# X4.net
KiCad netlist of a schematic drawn in Altium Designer
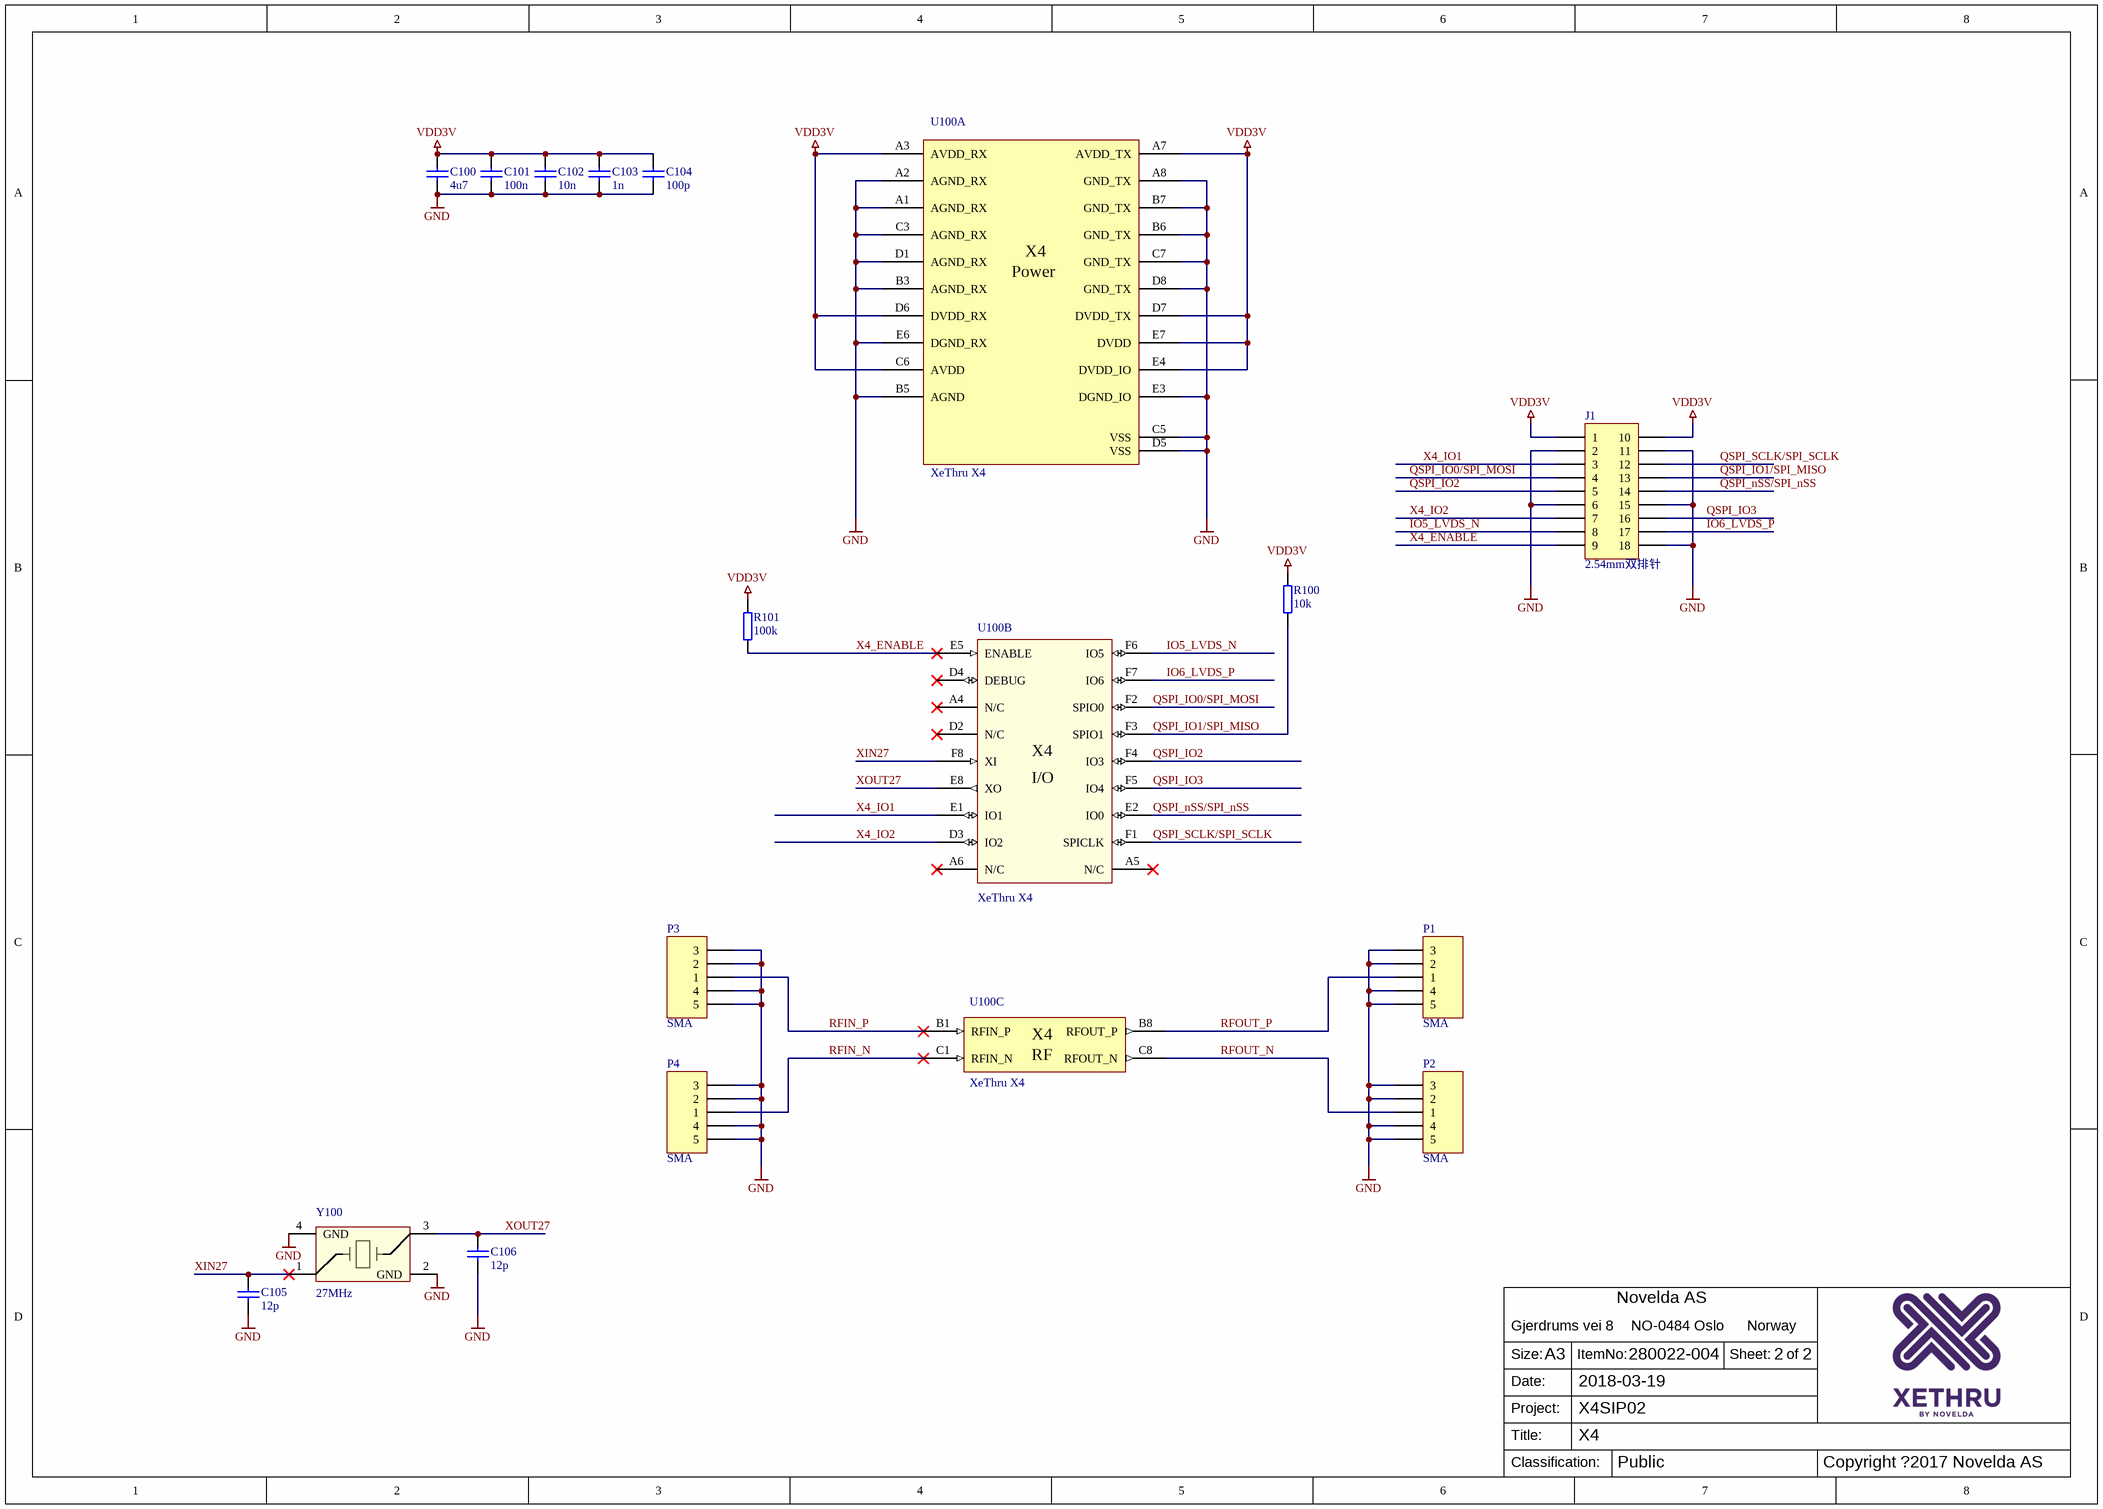
[diagram p0: X4.SchDoc]

(export (version "E")
  (design (tool "Eeschema 10.0.6"))
  (components
    (comp (ref "C100")
      (value "4u7")
      (footprint "0603-CAPACITOR-NONPOL")
      (description "CAPACITOR, 4u7, 0603, 10%, 10V, X5R")
      (fields (field (name "MANUFACTURER") "--"))
      (libsource (lib "novelda_altiumlib") (part "CAPACITOR-NONPOL"))
    )
    (comp (ref "C101")
      (value "100n")
      (footprint "0402-CAPACITOR-NONPOL")
      (description "CAPACITOR, 100n, 0402, 10%, 10V, X5R")
      (fields (field (name "MANUFACTURER") "--"))
      (libsource (lib "novelda_altiumlib") (part "CAPACITOR-NONPOL"))
    )
    (comp (ref "C102")
      (value "10n")
      (footprint "0402-CAPACITOR-NONPOL")
      (description "CAPACITOR, 10n, 0402, 10%, 25V, X7R")
      (fields (field (name "MANUFACTURER") "--"))
      (libsource (lib "novelda_altiumlib") (part "CAPACITOR-NONPOL"))
    )
    (comp (ref "C103")
      (value "1n")
      (footprint "0402-CAPACITOR-NONPOL")
      (description "CAPACITOR, 1n, 0402, 10%, 25V, X7R")
      (fields (field (name "MANUFACTURER") "--"))
      (libsource (lib "novelda_altiumlib") (part "CAPACITOR-NONPOL"))
    )
    (comp (ref "C104")
      (value "100p")
      (footprint "0402-CAPACITOR-NONPOL")
      (description "CAPACITOR, 100p, 0402, 20%, 50V, X7R")
      (fields (field (name "MANUFACTURER") "--"))
      (libsource (lib "novelda_altiumlib") (part "CAPACITOR-NONPOL"))
    )
    (comp (ref "C105")
      (value "12p")
      (footprint "0402-CAPACITOR-NONPOL")
      (description "CAPACITOR, 12p, 0402, 5%, 50V, NP0")
      (fields (field (name "MANUFACTURER") "--"))
      (libsource (lib "novelda_altiumlib") (part "CAPACITOR-NONPOL"))
    )
    (comp (ref "C106")
      (value "12p")
      (footprint "0402-CAPACITOR-NONPOL")
      (description "CAPACITOR, 12p, 0402, 5%, 50V, NP0")
      (fields (field (name "MANUFACTURER") "--"))
      (libsource (lib "novelda_altiumlib") (part "CAPACITOR-NONPOL"))
    )
    (comp (ref "J1")
      (value "2.54mm双排针")
      (footprint "HDR2X9_CEN")
      (description "Header, 9-Pin, Dual row")
      (fields (field (name "PUBLISHER") "Altium Limited"))
      (libsource (lib "Miscellaneous Connectors") (part "Header 9X2A"))
    )
    (comp (ref "P1")
      (value "SMA")
      (footprint "SMD3")
      (description "Header, 5-Pin")
      (fields (field (name "PUBLISHER") "Altium Limited"))
      (libsource (lib "Miscellaneous Connectors") (part "Header 5"))
    )
    (comp (ref "P2")
      (value "SMA")
      (footprint "SMD3")
      (description "Header, 5-Pin")
      (fields (field (name "PUBLISHER") "Altium Limited"))
      (libsource (lib "Miscellaneous Connectors") (part "Header 5"))
    )
    (comp (ref "P3")
      (value "SMA")
      (footprint "SMD3")
      (description "Header, 5-Pin")
      (fields (field (name "PUBLISHER") "Altium Limited"))
      (libsource (lib "") (part "Header 5_1"))
    )
    (comp (ref "P4")
      (value "SMA")
      (footprint "SMD3")
      (description "Header, 5-Pin")
      (fields (field (name "PUBLISHER") "Altium Limited"))
      (libsource (lib "") (part "Header 5_1"))
    )
    (comp (ref "R100")
      (value "10k")
      (footprint "0402-RESISTOR")
      (description "RESISTOR, 10k, 0402, 1%, 63mW")
      (fields (field (name "MANUFACTURER") "--"))
      (libsource (lib "novelda_altiumlib") (part "RESISTOR"))
    )
    (comp (ref "R101")
      (value "100k")
      (footprint "0402-RESISTOR")
      (description "RESISTOR, 100k, 0402, 1%, 63mW")
      (fields (field (name "MANUFACTURER") "--"))
      (libsource (lib "novelda_altiumlib") (part "RESISTOR"))
    )
    (comp (ref "U100")
      (value "XeThru X4")
      (footprint "200106-002")
      (fields (field (name "MANUFACTURER") "Novelda") (field (name "MPN") "200260-002"))
      (libsource (lib "novelda_altiumlib") (part "200260-002"))
    )
    (comp (ref "Y100")
      (value "27MHz")
      (footprint "200281")
      (description "LFXTAL072115, CRYSTAL 27MHZ, 10PF, SMD")
      (fields (field (name "MANUFACTURER") "IQD Frequency Products") (field (name "MPN") "LFXTAL072115"))
      (libsource (lib "novelda_altiumlib") (part "200281"))
    )
  )
  (nets
    (net (code "1") (name "/IO5_LVDS_N") (class "Default")
      (node (ref "J1") (pin "8") (pinfunction "8_8") (pintype "passive"))
      (node (ref "U100") (pin "F6") (pinfunction "IO5_F6") (pintype "bidirectional"))
    )
    (net (code "2") (name "/IO6_LVDS_P") (class "Default")
      (node (ref "J1") (pin "17") (pinfunction "17_17") (pintype "passive"))
      (node (ref "U100") (pin "F7") (pinfunction "IO6_F7") (pintype "bidirectional"))
    )
    (net (code "3") (name "/QSPI_IO0{slash}SPI_MOSI") (class "Default")
      (node (ref "J1") (pin "4") (pinfunction "4_4") (pintype "passive"))
      (node (ref "U100") (pin "F2") (pinfunction "SPIO0_F2") (pintype "bidirectional"))
    )
    (net (code "4") (name "/QSPI_IO1{slash}SPI_MISO") (class "Default")
      (node (ref "J1") (pin "13") (pinfunction "13_13") (pintype "passive"))
      (node (ref "R100") (pin "1") (pinfunction "1_1") (pintype "passive"))
      (node (ref "U100") (pin "F3") (pinfunction "SPIO1_F3") (pintype "bidirectional"))
    )
    (net (code "5") (name "/QSPI_IO2") (class "Default")
      (node (ref "J1") (pin "5") (pinfunction "5_5") (pintype "passive"))
      (node (ref "U100") (pin "F4") (pinfunction "IO3_F4") (pintype "bidirectional"))
    )
    (net (code "6") (name "/QSPI_IO3") (class "Default")
      (node (ref "J1") (pin "16") (pinfunction "16_16") (pintype "passive"))
      (node (ref "U100") (pin "F5") (pinfunction "IO4_F5") (pintype "bidirectional"))
    )
    (net (code "7") (name "/QSPI_SCLK{slash}SPI_SCLK") (class "Default")
      (node (ref "J1") (pin "12") (pinfunction "12_12") (pintype "passive"))
      (node (ref "U100") (pin "F1") (pinfunction "SPICLK_F1") (pintype "bidirectional"))
    )
    (net (code "8") (name "/QSPI_nSS{slash}SPI_nSS") (class "Default")
      (node (ref "J1") (pin "14") (pinfunction "14_14") (pintype "passive"))
      (node (ref "U100") (pin "E2") (pinfunction "IO0_E2") (pintype "bidirectional"))
    )
    (net (code "9") (name "/RFIN_N") (class "Default")
      (node (ref "P4") (pin "1") (pinfunction "1_1") (pintype "passive"))
      (node (ref "U100") (pin "C1") (pinfunction "RFIN_N_C1") (pintype "input"))
    )
    (net (code "10") (name "/RFIN_P") (class "Default")
      (node (ref "P3") (pin "1") (pinfunction "1_1") (pintype "passive"))
      (node (ref "U100") (pin "B1") (pinfunction "RFIN_P_B1") (pintype "input"))
    )
    (net (code "11") (name "/RFOUT_N") (class "Default")
      (node (ref "P2") (pin "1") (pinfunction "1_1") (pintype "passive"))
      (node (ref "U100") (pin "C8") (pinfunction "RFOUT_N_C8") (pintype "output"))
    )
    (net (code "12") (name "/RFOUT_P") (class "Default")
      (node (ref "P1") (pin "1") (pinfunction "1_1") (pintype "passive"))
      (node (ref "U100") (pin "B8") (pinfunction "RFOUT_P_B8") (pintype "output"))
    )
    (net (code "13") (name "/X4_ENABLE") (class "Default")
      (node (ref "J1") (pin "9") (pinfunction "9_9") (pintype "passive"))
      (node (ref "R101") (pin "1") (pinfunction "1_1") (pintype "passive"))
      (node (ref "U100") (pin "E5") (pinfunction "ENABLE_E5") (pintype "input"))
    )
    (net (code "14") (name "/X4_IO1") (class "Default")
      (node (ref "J1") (pin "3") (pinfunction "3_3") (pintype "passive"))
      (node (ref "U100") (pin "E1") (pinfunction "IO1_E1") (pintype "bidirectional"))
    )
    (net (code "15") (name "/X4_IO2") (class "Default")
      (node (ref "J1") (pin "7") (pinfunction "7_7") (pintype "passive"))
      (node (ref "U100") (pin "D3") (pinfunction "IO2_D3") (pintype "bidirectional"))
    )
    (net (code "16") (name "/XIN27") (class "Default")
      (node (ref "C105") (pin "1") (pinfunction "1_1") (pintype "passive"))
      (node (ref "U100") (pin "F8") (pinfunction "XI_F8") (pintype "input"))
      (node (ref "Y100") (pin "1") (pinfunction "1_1") (pintype "passive"))
    )
    (net (code "17") (name "/XOUT27") (class "Default")
      (node (ref "C106") (pin "1") (pinfunction "1_1") (pintype "passive"))
      (node (ref "U100") (pin "E8") (pinfunction "XO_E8") (pintype "output"))
      (node (ref "Y100") (pin "3") (pinfunction "3_3") (pintype "passive"))
    )
    (net (code "18") (name "GND") (class "Default")
      (node (ref "C100") (pin "2") (pinfunction "2_2") (pintype "passive"))
      (node (ref "C101") (pin "2") (pinfunction "2_2") (pintype "passive"))
      (node (ref "C102") (pin "2") (pinfunction "2_2") (pintype "passive"))
      (node (ref "C103") (pin "2") (pinfunction "2_2") (pintype "passive"))
      (node (ref "C104") (pin "2") (pinfunction "2_2") (pintype "passive"))
      (node (ref "C105") (pin "2") (pinfunction "2_2") (pintype "passive"))
      (node (ref "C106") (pin "2") (pinfunction "2_2") (pintype "passive"))
      (node (ref "J1") (pin "11") (pinfunction "11_11") (pintype "passive"))
      (node (ref "J1") (pin "15") (pinfunction "15_15") (pintype "passive"))
      (node (ref "J1") (pin "18") (pinfunction "18_18") (pintype "passive"))
      (node (ref "J1") (pin "2") (pinfunction "2_2") (pintype "passive"))
      (node (ref "J1") (pin "6") (pinfunction "6_6") (pintype "passive"))
      (node (ref "P1") (pin "2") (pinfunction "2_2") (pintype "passive"))
      (node (ref "P1") (pin "3") (pinfunction "3_3") (pintype "passive"))
      (node (ref "P1") (pin "4") (pinfunction "4_4") (pintype "passive"))
      (node (ref "P1") (pin "5") (pinfunction "5_5") (pintype "passive"))
      (node (ref "P2") (pin "2") (pinfunction "2_2") (pintype "passive"))
      (node (ref "P2") (pin "3") (pinfunction "3_3") (pintype "passive"))
      (node (ref "P2") (pin "4") (pinfunction "4_4") (pintype "passive"))
      (node (ref "P2") (pin "5") (pinfunction "5_5") (pintype "passive"))
      (node (ref "P3") (pin "2") (pinfunction "2_2") (pintype "passive"))
      (node (ref "P3") (pin "3") (pinfunction "3_3") (pintype "passive"))
      (node (ref "P3") (pin "4") (pinfunction "4_4") (pintype "passive"))
      (node (ref "P3") (pin "5") (pinfunction "5_5") (pintype "passive"))
      (node (ref "P4") (pin "2") (pinfunction "2_2") (pintype "passive"))
      (node (ref "P4") (pin "3") (pinfunction "3_3") (pintype "passive"))
      (node (ref "P4") (pin "4") (pinfunction "4_4") (pintype "passive"))
      (node (ref "P4") (pin "5") (pinfunction "5_5") (pintype "passive"))
      (node (ref "U100") (pin "A1") (pinfunction "AGND_RX_A1") (pintype "power_in"))
      (node (ref "U100") (pin "A2") (pinfunction "AGND_RX_A2") (pintype "power_in"))
      (node (ref "U100") (pin "A8") (pinfunction "GND_TX_A8") (pintype "power_in"))
      (node (ref "U100") (pin "B3") (pinfunction "AGND_RX_B3") (pintype "power_in"))
      (node (ref "U100") (pin "B5") (pinfunction "AGND_B5") (pintype "power_in"))
      (node (ref "U100") (pin "B6") (pinfunction "GND_TX_B6") (pintype "power_in"))
      (node (ref "U100") (pin "B7") (pinfunction "GND_TX_B7") (pintype "power_in"))
      (node (ref "U100") (pin "C3") (pinfunction "AGND_RX_C3") (pintype "power_in"))
      (node (ref "U100") (pin "C5") (pinfunction "VSS_C5") (pintype "power_in"))
      (node (ref "U100") (pin "C7") (pinfunction "GND_TX_C7") (pintype "power_in"))
      (node (ref "U100") (pin "D1") (pinfunction "AGND_RX_D1") (pintype "power_in"))
      (node (ref "U100") (pin "D5") (pinfunction "VSS_D5") (pintype "power_in"))
      (node (ref "U100") (pin "D8") (pinfunction "GND_TX_D8") (pintype "power_in"))
      (node (ref "U100") (pin "E3") (pinfunction "DGND_IO_E3") (pintype "power_in"))
      (node (ref "U100") (pin "E6") (pinfunction "DGND_RX_E6") (pintype "power_in"))
      (node (ref "Y100") (pin "2") (pinfunction "GND_2") (pintype "passive"))
      (node (ref "Y100") (pin "4") (pinfunction "GND_4") (pintype "passive"))
    )
    (net (code "19") (name "VDD3V") (class "Default")
      (node (ref "C100") (pin "1") (pinfunction "1_1") (pintype "passive"))
      (node (ref "C101") (pin "1") (pinfunction "1_1") (pintype "passive"))
      (node (ref "C102") (pin "1") (pinfunction "1_1") (pintype "passive"))
      (node (ref "C103") (pin "1") (pinfunction "1_1") (pintype "passive"))
      (node (ref "C104") (pin "1") (pinfunction "1_1") (pintype "passive"))
      (node (ref "J1") (pin "1") (pinfunction "1_1") (pintype "passive"))
      (node (ref "J1") (pin "10") (pinfunction "10_10") (pintype "passive"))
      (node (ref "R100") (pin "2") (pinfunction "2_2") (pintype "passive"))
      (node (ref "R101") (pin "2") (pinfunction "2_2") (pintype "passive"))
      (node (ref "U100") (pin "A3") (pinfunction "AVDD_RX_A3") (pintype "power_in"))
      (node (ref "U100") (pin "A7") (pinfunction "AVDD_TX_A7") (pintype "power_in"))
      (node (ref "U100") (pin "C6") (pinfunction "AVDD_C6") (pintype "power_in"))
      (node (ref "U100") (pin "D6") (pinfunction "DVDD_RX_D6") (pintype "power_in"))
      (node (ref "U100") (pin "D7") (pinfunction "DVDD_TX_D7") (pintype "power_in"))
      (node (ref "U100") (pin "E4") (pinfunction "DVDD_IO_E4") (pintype "power_in"))
      (node (ref "U100") (pin "E7") (pinfunction "DVDD_E7") (pintype "power_in"))
    )
    (net (code "20") (name "unconnected-(U100B-DEBUG-PadD4)") (class "Default")
      (node (ref "U100") (pin "D4") (pinfunction "DEBUG_D4") (pintype "bidirectional+no_connect"))
    )
    (net (code "21") (name "unconnected-(U100B-N{slash}C-PadA4)") (class "Default")
      (node (ref "U100") (pin "A4") (pinfunction "N/C_A4") (pintype "passive+no_connect"))
    )
    (net (code "22") (name "unconnected-(U100B-N{slash}C-PadA5)") (class "Default")
      (node (ref "U100") (pin "A5") (pinfunction "N/C_A5") (pintype "passive+no_connect"))
    )
    (net (code "23") (name "unconnected-(U100B-N{slash}C-PadA6)") (class "Default")
      (node (ref "U100") (pin "A6") (pinfunction "N/C_A6") (pintype "passive+no_connect"))
    )
    (net (code "24") (name "unconnected-(U100B-N{slash}C-PadD2)") (class "Default")
      (node (ref "U100") (pin "D2") (pinfunction "N/C_D2") (pintype "passive+no_connect"))
    )
  )
)
